# arduino_cw_nano_keyer.net
KiCad netlist of a schematic drawn in EAGLE
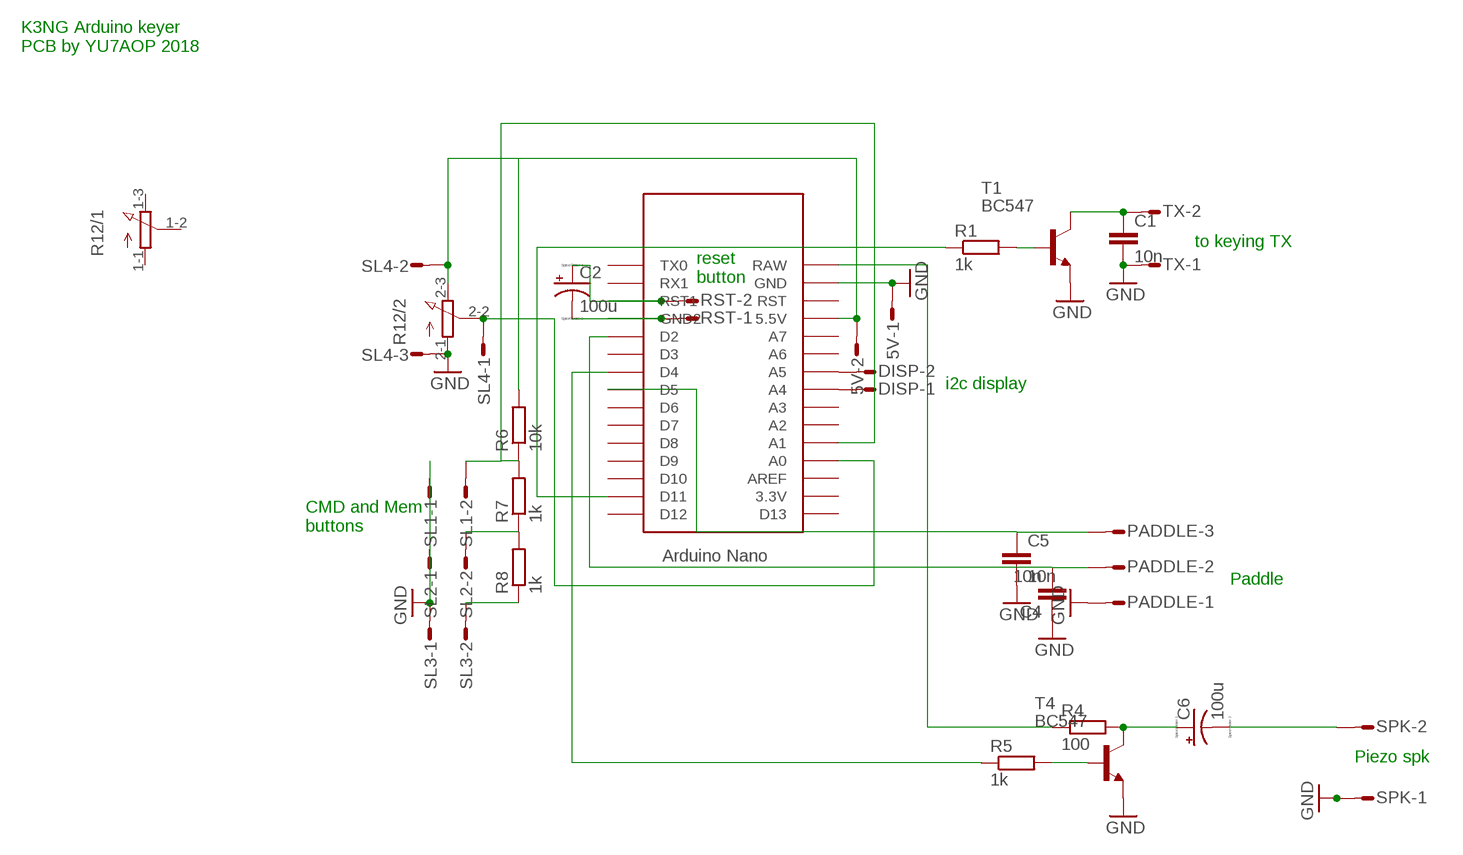
[diagram p0: schematic, sheet 1]

(export (version "E")
  (design (tool "Eeschema 10.0.6"))
  (components
    (comp (ref "5V")
      (value "M02S")
      (footprint "eagle-import:02P")
      (libsource (lib "eagle-import") (part "M02S"))
    )
    (comp (ref "C1")
      (value "10n")
      (footprint "eagle-import:C050-025X075")
      (libsource (lib "eagle-import") (part "C-EU050-025X075"))
    )
    (comp (ref "C2")
      (value "100u")
      (footprint "eagle-import:E2,5-5")
      (libsource (lib "eagle-import") (part "CPOL-USE2.5-5"))
    )
    (comp (ref "C4")
      (value "10n")
      (footprint "eagle-import:C050-025X075")
      (libsource (lib "eagle-import") (part "C-EU050-025X075"))
    )
    (comp (ref "C5")
      (value "10n")
      (footprint "eagle-import:C050-025X075")
      (libsource (lib "eagle-import") (part "C-EU050-025X075"))
    )
    (comp (ref "C6")
      (value "100u")
      (footprint "eagle-import:E2,5-5")
      (libsource (lib "eagle-import") (part "CPOL-USE2.5-5"))
    )
    (comp (ref "DISP")
      (value "M02S")
      (footprint "eagle-import:02P")
      (libsource (lib "eagle-import") (part "M02S"))
    )
    (comp (ref "PADDLE")
      (value "M03S")
      (footprint "eagle-import:03P")
      (libsource (lib "eagle-import") (part "M03S"))
    )
    (comp (ref "R1")
      (value "1k")
      (footprint "eagle-import:0207_10")
      (libsource (lib "eagle-import") (part "R-EU_0207/10"))
    )
    (comp (ref "R4")
      (value "100")
      (footprint "eagle-import:0207_10")
      (libsource (lib "eagle-import") (part "R-EU_0207/10"))
    )
    (comp (ref "R5")
      (value "1k")
      (footprint "eagle-import:0207_10")
      (libsource (lib "eagle-import") (part "R-EU_0207/10"))
    )
    (comp (ref "R6")
      (value "10k")
      (footprint "eagle-import:0207_10")
      (libsource (lib "eagle-import") (part "R-EU_0207/10"))
    )
    (comp (ref "R7")
      (value "1k")
      (footprint "eagle-import:0207_10")
      (libsource (lib "eagle-import") (part "R-EU_0207/10"))
    )
    (comp (ref "R8")
      (value "1k")
      (footprint "eagle-import:0207_10")
      (libsource (lib "eagle-import") (part "R-EU_0207/10"))
    )
    (comp (ref "R12")
      (value "3RP/1610G")
      (footprint "eagle-import:3RP_1610G")
      (libsource (lib "eagle-import") (part "3RP/1610G"))
    )
    (comp (ref "RST")
      (value "M02S")
      (footprint "eagle-import:02P")
      (libsource (lib "eagle-import") (part "M02S"))
    )
    (comp (ref "SL1")
      (value "M02S")
      (footprint "eagle-import:02P")
      (libsource (lib "eagle-import") (part "M02S"))
    )
    (comp (ref "SL2")
      (value "M02S")
      (footprint "eagle-import:02P")
      (libsource (lib "eagle-import") (part "M02S"))
    )
    (comp (ref "SL3")
      (value "M02S")
      (footprint "eagle-import:02P")
      (libsource (lib "eagle-import") (part "M02S"))
    )
    (comp (ref "SL4")
      (value "M03S")
      (footprint "eagle-import:03P")
      (libsource (lib "eagle-import") (part "M03S"))
    )
    (comp (ref "SPK")
      (value "M02S")
      (footprint "eagle-import:02P")
      (libsource (lib "eagle-import") (part "M02S"))
    )
    (comp (ref "T1")
      (value "BC547")
      (footprint "eagle-import:TO92")
      (libsource (lib "eagle-import") (part "BC547"))
    )
    (comp (ref "T4")
      (value "BC547")
      (footprint "eagle-import:TO92")
      (libsource (lib "eagle-import") (part "BC547"))
    )
    (comp (ref "TX")
      (value "M02S")
      (footprint "eagle-import:02P")
      (libsource (lib "eagle-import") (part "M02S"))
    )
    (comp (ref "U$1")
      (value "NANO")
      (footprint "eagle-import:NANO")
      (libsource (lib "eagle-import") (part "NANO"))
    )
  )
  (nets
    (net (code "1") (name "GND") (class "Default")
      (node (ref "5V") (pin "1") (pinfunction "S_1") (pintype "passive"))
      (node (ref "C1") (pin "2") (pinfunction "2_2") (pintype "passive"))
      (node (ref "C4") (pin "1") (pinfunction "1_1") (pintype "passive"))
      (node (ref "C5") (pin "2") (pinfunction "2_2") (pintype "passive"))
      (node (ref "PADDLE") (pin "1") (pinfunction "S_1") (pintype "passive"))
      (node (ref "R12") (pin "2-1") (pinfunction "A_2-1") (pintype "passive"))
      (node (ref "SL1") (pin "1") (pinfunction "S_1") (pintype "passive"))
      (node (ref "SL2") (pin "1") (pinfunction "S_1") (pintype "passive"))
      (node (ref "SL3") (pin "1") (pinfunction "S_1") (pintype "passive"))
      (node (ref "SL4") (pin "3") (pinfunction "S_3") (pintype "passive"))
      (node (ref "SPK") (pin "1") (pinfunction "S_1") (pintype "passive"))
      (node (ref "T1") (pin "1") (pinfunction "E_1") (pintype "passive"))
      (node (ref "T4") (pin "1") (pinfunction "E_1") (pintype "passive"))
      (node (ref "TX") (pin "1") (pinfunction "S_1") (pintype "passive"))
      (node (ref "U$1") (pin "GND") (pinfunction "GND_GND") (pintype "bidirectional"))
    )
    (net (code "2") (name "Net-(5VB-S)") (class "Default")
      (node (ref "5V") (pin "2") (pinfunction "S_2") (pintype "passive"))
      (node (ref "R12") (pin "2-3") (pinfunction "E_2-3") (pintype "passive"))
      (node (ref "R6") (pin "2") (pinfunction "2_2") (pintype "passive"))
      (node (ref "SL4") (pin "2") (pinfunction "S_2") (pintype "passive"))
      (node (ref "U$1") (pin "5V") (pinfunction "5.5V_5V") (pintype "bidirectional"))
    )
    (net (code "3") (name "Net-(DISPA-S)") (class "Default")
      (node (ref "DISP") (pin "1") (pinfunction "S_1") (pintype "passive"))
      (node (ref "U$1") (pin "A4") (pinfunction "A4_A4") (pintype "bidirectional"))
    )
    (net (code "4") (name "Net-(DISPB-S)") (class "Default")
      (node (ref "DISP") (pin "2") (pinfunction "S_2") (pintype "passive"))
      (node (ref "U$1") (pin "A5") (pinfunction "A5_A5") (pintype "bidirectional"))
    )
    (net (code "5") (name "Net-(PADDLEB-S)") (class "Default")
      (node (ref "C4") (pin "2") (pinfunction "2_2") (pintype "passive"))
      (node (ref "PADDLE") (pin "2") (pinfunction "S_2") (pintype "passive"))
      (node (ref "U$1") (pin "D2") (pinfunction "D2_D2") (pintype "bidirectional"))
    )
    (net (code "6") (name "Net-(PADDLEC-S)") (class "Default")
      (node (ref "C5") (pin "1") (pinfunction "1_1") (pintype "passive"))
      (node (ref "PADDLE") (pin "3") (pinfunction "S_3") (pintype "passive"))
      (node (ref "U$1") (pin "D5") (pinfunction "D5_D5") (pintype "bidirectional"))
    )
    (net (code "7") (name "Net-(R1-Pad1)") (class "Default")
      (node (ref "R1") (pin "1") (pinfunction "1_1") (pintype "passive"))
      (node (ref "U$1") (pin "D11") (pinfunction "D11_D11") (pintype "bidirectional"))
    )
    (net (code "8") (name "Net-(R4-Pad1)") (class "Default")
      (node (ref "R4") (pin "1") (pinfunction "1_1") (pintype "passive"))
      (node (ref "U$1") (pin "RAW") (pinfunction "RAW_RAW") (pintype "bidirectional"))
    )
    (net (code "9") (name "Net-(R5-Pad1)") (class "Default")
      (node (ref "R5") (pin "1") (pinfunction "1_1") (pintype "passive"))
      (node (ref "U$1") (pin "D4") (pinfunction "D4_D4") (pintype "bidirectional"))
    )
    (net (code "10") (name "Net-(R12B-S)") (class "Default")
      (node (ref "R12") (pin "2-2") (pinfunction "S_2-2") (pintype "passive"))
      (node (ref "SL4") (pin "1") (pinfunction "S_1") (pintype "passive"))
      (node (ref "U$1") (pin "A0") (pinfunction "A0_A0") (pintype "bidirectional"))
    )
    (net (code "11") (name "Net-(RSTA-S)") (class "Default")
      (node (ref "C2") (pin "-") (pinfunction "-_-") (pintype "passive"))
      (node (ref "RST") (pin "1") (pinfunction "S_1") (pintype "passive"))
      (node (ref "U$1") (pin "GND1") (pinfunction "GND2_GND1") (pintype "bidirectional"))
    )
    (net (code "12") (name "Net-(RSTB-S)") (class "Default")
      (node (ref "C2") (pin "+") (pinfunction "+_+") (pintype "passive"))
      (node (ref "RST") (pin "2") (pinfunction "S_2") (pintype "passive"))
      (node (ref "U$1") (pin "RST1") (pinfunction "RST1_RST1") (pintype "bidirectional"))
    )
    (net (code "13") (name "Net-(SL1B-S)") (class "Default")
      (node (ref "R6") (pin "1") (pinfunction "1_1") (pintype "passive"))
      (node (ref "R7") (pin "2") (pinfunction "2_2") (pintype "passive"))
      (node (ref "SL1") (pin "2") (pinfunction "S_2") (pintype "passive"))
      (node (ref "U$1") (pin "A1") (pinfunction "A1_A1") (pintype "bidirectional"))
    )
    (net (code "14") (name "Net-(SL2B-S)") (class "Default")
      (node (ref "R7") (pin "1") (pinfunction "1_1") (pintype "passive"))
      (node (ref "R8") (pin "2") (pinfunction "2_2") (pintype "passive"))
      (node (ref "SL2") (pin "2") (pinfunction "S_2") (pintype "passive"))
    )
    (net (code "15") (name "Net-(SL3B-S)") (class "Default")
      (node (ref "R8") (pin "1") (pinfunction "1_1") (pintype "passive"))
      (node (ref "SL3") (pin "2") (pinfunction "S_2") (pintype "passive"))
    )
    (net (code "16") (name "Net-(SPKB-S)") (class "Default")
      (node (ref "C6") (pin "-") (pinfunction "-_-") (pintype "passive"))
      (node (ref "SPK") (pin "2") (pinfunction "S_2") (pintype "passive"))
    )
    (net (code "17") (name "Net-(T1-B)") (class "Default")
      (node (ref "R1") (pin "2") (pinfunction "2_2") (pintype "passive"))
      (node (ref "T1") (pin "2") (pinfunction "B_2") (pintype "passive"))
    )
    (net (code "18") (name "Net-(T1-C)") (class "Default")
      (node (ref "C1") (pin "1") (pinfunction "1_1") (pintype "passive"))
      (node (ref "T1") (pin "3") (pinfunction "C_3") (pintype "passive"))
      (node (ref "TX") (pin "2") (pinfunction "S_2") (pintype "passive"))
    )
    (net (code "19") (name "Net-(T4-B)") (class "Default")
      (node (ref "R5") (pin "2") (pinfunction "2_2") (pintype "passive"))
      (node (ref "T4") (pin "2") (pinfunction "B_2") (pintype "passive"))
    )
    (net (code "20") (name "Net-(T4-C)") (class "Default")
      (node (ref "C6") (pin "+") (pinfunction "+_+") (pintype "passive"))
      (node (ref "R4") (pin "2") (pinfunction "2_2") (pintype "passive"))
      (node (ref "T4") (pin "3") (pinfunction "C_3") (pintype "passive"))
    )
    (net (code "21") (name "unconnected-(R12A-A-Pad1-1)") (class "Default")
      (node (ref "R12") (pin "1-1") (pinfunction "A_1-1") (pintype "passive"))
    )
    (net (code "22") (name "unconnected-(R12A-E-Pad1-3)") (class "Default")
      (node (ref "R12") (pin "1-3") (pinfunction "E_1-3") (pintype "passive"))
    )
    (net (code "23") (name "unconnected-(R12A-S-Pad1-2)") (class "Default")
      (node (ref "R12") (pin "1-2") (pinfunction "S_1-2") (pintype "passive"))
    )
    (net (code "24") (name "unconnected-(U$1-Pad3.3V)") (class "Default")
      (node (ref "U$1") (pin "3.3V") (pinfunction "3.3V_3.3V") (pintype "bidirectional"))
    )
    (net (code "25") (name "unconnected-(U$1-PadA2)") (class "Default")
      (node (ref "U$1") (pin "A2") (pinfunction "A2_A2") (pintype "bidirectional"))
    )
    (net (code "26") (name "unconnected-(U$1-PadA3)") (class "Default")
      (node (ref "U$1") (pin "A3") (pinfunction "A3_A3") (pintype "bidirectional"))
    )
    (net (code "27") (name "unconnected-(U$1-PadA6)") (class "Default")
      (node (ref "U$1") (pin "A6") (pinfunction "A6_A6") (pintype "bidirectional"))
    )
    (net (code "28") (name "unconnected-(U$1-PadA7)") (class "Default")
      (node (ref "U$1") (pin "A7") (pinfunction "A7_A7") (pintype "bidirectional"))
    )
    (net (code "29") (name "unconnected-(U$1-PadAREF)") (class "Default")
      (node (ref "U$1") (pin "AREF") (pinfunction "AREF_AREF") (pintype "bidirectional"))
    )
    (net (code "30") (name "unconnected-(U$1-PadD3)") (class "Default")
      (node (ref "U$1") (pin "D3") (pinfunction "D3_D3") (pintype "bidirectional"))
    )
    (net (code "31") (name "unconnected-(U$1-PadD6)") (class "Default")
      (node (ref "U$1") (pin "D6") (pinfunction "D6_D6") (pintype "bidirectional"))
    )
    (net (code "32") (name "unconnected-(U$1-PadD7)") (class "Default")
      (node (ref "U$1") (pin "D7") (pinfunction "D7_D7") (pintype "bidirectional"))
    )
    (net (code "33") (name "unconnected-(U$1-PadD8)") (class "Default")
      (node (ref "U$1") (pin "D8") (pinfunction "D8_D8") (pintype "bidirectional"))
    )
    (net (code "34") (name "unconnected-(U$1-PadD9)") (class "Default")
      (node (ref "U$1") (pin "D9") (pinfunction "D9_D9") (pintype "bidirectional"))
    )
    (net (code "35") (name "unconnected-(U$1-PadD10)") (class "Default")
      (node (ref "U$1") (pin "D10") (pinfunction "D10_D10") (pintype "bidirectional"))
    )
    (net (code "36") (name "unconnected-(U$1-PadD12)") (class "Default")
      (node (ref "U$1") (pin "D12") (pinfunction "D12_D12") (pintype "bidirectional"))
    )
    (net (code "37") (name "unconnected-(U$1-PadD13)") (class "Default")
      (node (ref "U$1") (pin "D13") (pinfunction "D13_D13") (pintype "bidirectional"))
    )
    (net (code "38") (name "unconnected-(U$1-PadICSP1)") (class "Default")
      (node (ref "U$1") (pin "ICSP1") (pinfunction "ICSP1_ICSP1") (pintype "bidirectional"))
    )
    (net (code "39") (name "unconnected-(U$1-PadICSP2)") (class "Default")
      (node (ref "U$1") (pin "ICSP2") (pinfunction "ICSP2_ICSP2") (pintype "bidirectional"))
    )
    (net (code "40") (name "unconnected-(U$1-PadICSP3)") (class "Default")
      (node (ref "U$1") (pin "ICSP3") (pinfunction "ICSP3_ICSP3") (pintype "bidirectional"))
    )
    (net (code "41") (name "unconnected-(U$1-PadICSP4)") (class "Default")
      (node (ref "U$1") (pin "ICSP4") (pinfunction "ICSP4_ICSP4") (pintype "bidirectional"))
    )
    (net (code "42") (name "unconnected-(U$1-PadICSP5)") (class "Default")
      (node (ref "U$1") (pin "ICSP5") (pinfunction "ICSP5_ICSP5") (pintype "bidirectional"))
    )
    (net (code "43") (name "unconnected-(U$1-PadICSP6)") (class "Default")
      (node (ref "U$1") (pin "ICSP6") (pinfunction "ICSP6_ICSP6") (pintype "bidirectional"))
    )
    (net (code "44") (name "unconnected-(U$1-PadRST)") (class "Default")
      (node (ref "U$1") (pin "RST") (pinfunction "RST_RST") (pintype "bidirectional"))
    )
    (net (code "45") (name "unconnected-(U$1-PadRX1)") (class "Default")
      (node (ref "U$1") (pin "RX1") (pinfunction "RX1_RX1") (pintype "bidirectional"))
    )
    (net (code "46") (name "unconnected-(U$1-PadTX0)") (class "Default")
      (node (ref "U$1") (pin "TX0") (pinfunction "TX0_TX0") (pintype "bidirectional"))
    )
  )
)
